# 07-AudioAmplifier_TDA7297.net
KiCad netlist of a schematic drawn in Altium Designer
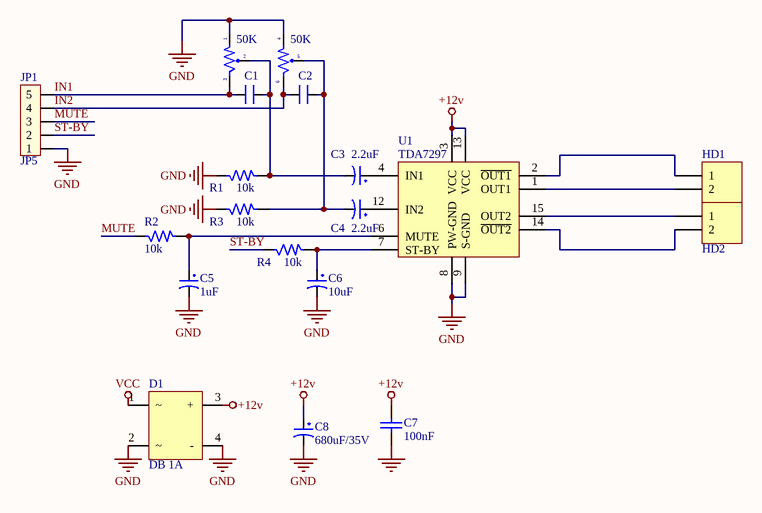
[diagram p0: 07-AudioAmplifier(TDA7297).SchDoc]

(export (version "E")
  (design (tool "Eeschema 10.0.6"))
  (components
    (comp (ref "C1")
      (value "220nF")
      (footprint "C-0805")
      (fields (field (name "DESIGNED BY") "VanDungEvn"))
      (libsource (lib "syhaunguyen") (part "CN"))
    )
    (comp (ref "C2")
      (value "220nF")
      (footprint "C-0805")
      (fields (field (name "DESIGNED BY") "VanDungEvn"))
      (libsource (lib "syhaunguyen") (part "CN"))
    )
    (comp (ref "C3")
      (value "2.2uF")
      (footprint "ALU-4X5mm")
      (description "Cap P  0,1uF < 22uF , 16 - 50V")
      (libsource (lib "syhaunguyen") (part "CP1"))
    )
    (comp (ref "C4")
      (value "2.2uF")
      (footprint "ALU-4X5mm")
      (description "Cap P  0,1uF < 22uF , 16 - 50V")
      (libsource (lib "syhaunguyen") (part "CP1"))
    )
    (comp (ref "C5")
      (value "1uF")
      (footprint "ALU-4X5mm")
      (description "Cap P  0,1uF < 22uF , 16 - 50V")
      (libsource (lib "") (part "CP1_1"))
    )
    (comp (ref "C6")
      (value "10uF")
      (footprint "ALU-4X5mm")
      (description "Cap P  0,1uF < 22uF , 16 - 50V")
      (libsource (lib "") (part "CP1_1"))
    )
    (comp (ref "C7")
      (value "100nF")
      (footprint "RAD-0.3")
      (description "Capacitor")
      (fields (field (name "Comment") "104") (field (name "PUBLISHER") "Altium Limited"))
      (libsource (lib "Miscellaneous Devices") (part "Cap"))
    )
    (comp (ref "C8")
      (value "680uF/35V")
      (footprint "C-16x26mm")
      (description "Cap 1000uF/16V - 220uF/50V")
      (libsource (lib "syhaunguyen") (part "CP4"))
    )
    (comp (ref "D1")
      (value "DB 1A")
      (footprint "D-DB-DF06S-E3-45")
      (libsource (lib "doAnTotNghiep2017Lib") (part "DB"))
    )
    (comp (ref "HD1")
      (value "Header 2")
      (footprint "TER-KF301-2")
      (description "Header, 2-Pin")
      (fields (field (name "MANUFACTURER") "Generic Components"))
      (libsource (lib "syhaunguyen") (part "Header 2"))
    )
    (comp (ref "HD2")
      (value "Header 2")
      (footprint "TER-KF301-2")
      (description "Header, 2-Pin")
      (fields (field (name "MANUFACTURER") "Generic Components"))
      (libsource (lib "syhaunguyen") (part "Header 2"))
    )
    (comp (ref "JP1") (value "JP5") (footprint "JP5") (libsource (lib "syhaunguyen") (part "JP5")))
    (comp (ref "R1")
      (value "10k")
      (footprint "R-0805")
      (description "Resistor 1/4W")
      (libsource (lib "syhaunguyen") (part "R"))
    )
    (comp (ref "R2")
      (value "10k")
      (footprint "R-0805")
      (description "Resistor 1/4W")
      (libsource (lib "syhaunguyen") (part "R"))
    )
    (comp (ref "R3")
      (value "10k")
      (footprint "R-0805")
      (description "Resistor 1/4W")
      (libsource (lib "syhaunguyen") (part "R"))
    )
    (comp (ref "R4")
      (value "10k")
      (footprint "R-0805")
      (description "Resistor 1/4W")
      (libsource (lib "syhaunguyen") (part "R"))
    )
    (comp (ref "U1")
      (value "TDA7297")
      (footprint "MULTIWATT-15V")
      (libsource (lib "doAnTotNghiep2017Lib") (part "TDA7297"))
    )
    (comp (ref "VOL1")
      (value "50K")
      (footprint "VOL-D")
      (description "Volume control Dual")
      (libsource (lib "PART") (part "VOL-D"))
    )
  )
  (nets
    (net (code "1") (name "+12v") (class "Default")
      (node (ref "C7") (pin "1") (pinfunction "1_1") (pintype "passive"))
      (node (ref "C8") (pin "1") (pinfunction "1_1") (pintype "passive"))
      (node (ref "D1") (pin "3") (pinfunction "+_3") (pintype "passive"))
      (node (ref "U1") (pin "13") (pinfunction "VCC_13") (pintype "passive"))
      (node (ref "U1") (pin "3") (pinfunction "VCC_3") (pintype "passive"))
    )
    (net (code "2") (name "/IN1") (class "Default")
      (node (ref "C1") (pin "2") (pinfunction "2_2") (pintype "passive"))
      (node (ref "JP1") (pin "5") (pinfunction "5_5") (pintype "passive"))
      (node (ref "VOL1") (pin "3") (pinfunction "3_3") (pintype "passive"))
    )
    (net (code "3") (name "/IN2") (class "Default")
      (node (ref "C2") (pin "2") (pinfunction "2_2") (pintype "passive"))
      (node (ref "JP1") (pin "4") (pinfunction "4_4") (pintype "passive"))
      (node (ref "VOL1") (pin "6") (pinfunction "6_6") (pintype "passive"))
    )
    (net (code "4") (name "/MUTE") (class "Default")
      (node (ref "JP1") (pin "3") (pinfunction "3_3") (pintype "passive"))
      (node (ref "R2") (pin "1") (pinfunction "1_1") (pintype "passive"))
    )
    (net (code "5") (name "/ST-BY") (class "Default")
      (node (ref "JP1") (pin "2") (pinfunction "2_2") (pintype "passive"))
      (node (ref "R4") (pin "1") (pinfunction "1_1") (pintype "passive"))
    )
    (net (code "6") (name "GND") (class "Default")
      (node (ref "C5") (pin "2") (pinfunction "2_2") (pintype "passive"))
      (node (ref "C6") (pin "2") (pinfunction "2_2") (pintype "passive"))
      (node (ref "C7") (pin "2") (pinfunction "2_2") (pintype "passive"))
      (node (ref "C8") (pin "2") (pinfunction "2_2") (pintype "passive"))
      (node (ref "D1") (pin "2") (pinfunction "~_2") (pintype "passive"))
      (node (ref "D1") (pin "4") (pinfunction "-_4") (pintype "passive"))
      (node (ref "JP1") (pin "1") (pinfunction "1_1") (pintype "passive"))
      (node (ref "R1") (pin "1") (pinfunction "1_1") (pintype "passive"))
      (node (ref "R3") (pin "1") (pinfunction "1_1") (pintype "passive"))
      (node (ref "U1") (pin "8") (pinfunction "PW-GND_8") (pintype "passive"))
      (node (ref "U1") (pin "9") (pinfunction "S-GND_9") (pintype "passive"))
      (node (ref "VOL1") (pin "1") (pinfunction "1_1") (pintype "passive"))
      (node (ref "VOL1") (pin "4") (pinfunction "4_4") (pintype "passive"))
    )
    (net (code "7") (name "Net-(C1-Pad1)") (class "Default")
      (node (ref "C1") (pin "1") (pinfunction "1_1") (pintype "passive"))
      (node (ref "C3") (pin "2") (pinfunction "2_2") (pintype "passive"))
      (node (ref "R1") (pin "2") (pinfunction "2_2") (pintype "passive"))
      (node (ref "VOL1") (pin "2") (pinfunction "2_2") (pintype "passive"))
    )
    (net (code "8") (name "Net-(C2-Pad1)") (class "Default")
      (node (ref "C2") (pin "1") (pinfunction "1_1") (pintype "passive"))
      (node (ref "C4") (pin "2") (pinfunction "2_2") (pintype "passive"))
      (node (ref "R3") (pin "2") (pinfunction "2_2") (pintype "passive"))
      (node (ref "VOL1") (pin "5") (pinfunction "5_5") (pintype "passive"))
    )
    (net (code "9") (name "Net-(U1-IN1)") (class "Default")
      (node (ref "C3") (pin "1") (pinfunction "1_1") (pintype "passive"))
      (node (ref "U1") (pin "4") (pinfunction "IN1_4") (pintype "passive"))
    )
    (net (code "10") (name "Net-(U1-IN2)") (class "Default")
      (node (ref "C4") (pin "1") (pinfunction "1_1") (pintype "passive"))
      (node (ref "U1") (pin "12") (pinfunction "IN2_12") (pintype "passive"))
    )
    (net (code "11") (name "Net-(U1-MUTE)") (class "Default")
      (node (ref "C5") (pin "1") (pinfunction "1_1") (pintype "passive"))
      (node (ref "R2") (pin "2") (pinfunction "2_2") (pintype "passive"))
      (node (ref "U1") (pin "6") (pinfunction "MUTE_6") (pintype "passive"))
    )
    (net (code "12") (name "Net-(U1-OUT1)") (class "Default")
      (node (ref "HD1") (pin "2") (pinfunction "2_2") (pintype "passive"))
      (node (ref "U1") (pin "1") (pinfunction "OUT1_1") (pintype "passive"))
    )
    (net (code "13") (name "Net-(U1-OUT2)") (class "Default")
      (node (ref "HD2") (pin "1") (pinfunction "1_1") (pintype "passive"))
      (node (ref "U1") (pin "15") (pinfunction "OUT2_15") (pintype "passive"))
    )
    (net (code "14") (name "Net-(U1-ST-BY)") (class "Default")
      (node (ref "C6") (pin "1") (pinfunction "1_1") (pintype "passive"))
      (node (ref "R4") (pin "2") (pinfunction "2_2") (pintype "passive"))
      (node (ref "U1") (pin "7") (pinfunction "ST-BY_7") (pintype "passive"))
    )
    (net (code "15") (name "Net-(U1-~{OUT1})") (class "Default")
      (node (ref "HD1") (pin "1") (pinfunction "1_1") (pintype "passive"))
      (node (ref "U1") (pin "2") (pinfunction "~{OUT1}_2") (pintype "passive"))
    )
    (net (code "16") (name "Net-(U1-~{OUT2})") (class "Default")
      (node (ref "HD2") (pin "2") (pinfunction "2_2") (pintype "passive"))
      (node (ref "U1") (pin "14") (pinfunction "~{OUT2}_14") (pintype "passive"))
    )
    (net (code "17") (name "VCC") (class "Default")
      (node (ref "D1") (pin "1") (pinfunction "~_1") (pintype "passive"))
    )
    (net (code "18") (name "unconnected-(U1-NC-Pad5)") (class "Default")
      (node (ref "U1") (pin "5") (pinfunction "NC_5") (pintype "passive"))
    )
    (net (code "19") (name "unconnected-(U1-NC-Pad10)") (class "Default")
      (node (ref "U1") (pin "10") (pinfunction "NC_10") (pintype "passive"))
    )
    (net (code "20") (name "unconnected-(U1-NC-Pad11)") (class "Default")
      (node (ref "U1") (pin "11") (pinfunction "NC_11") (pintype "passive"))
    )
  )
)
